# FPGA1.net
KiCad netlist of a schematic drawn in Altium Designer
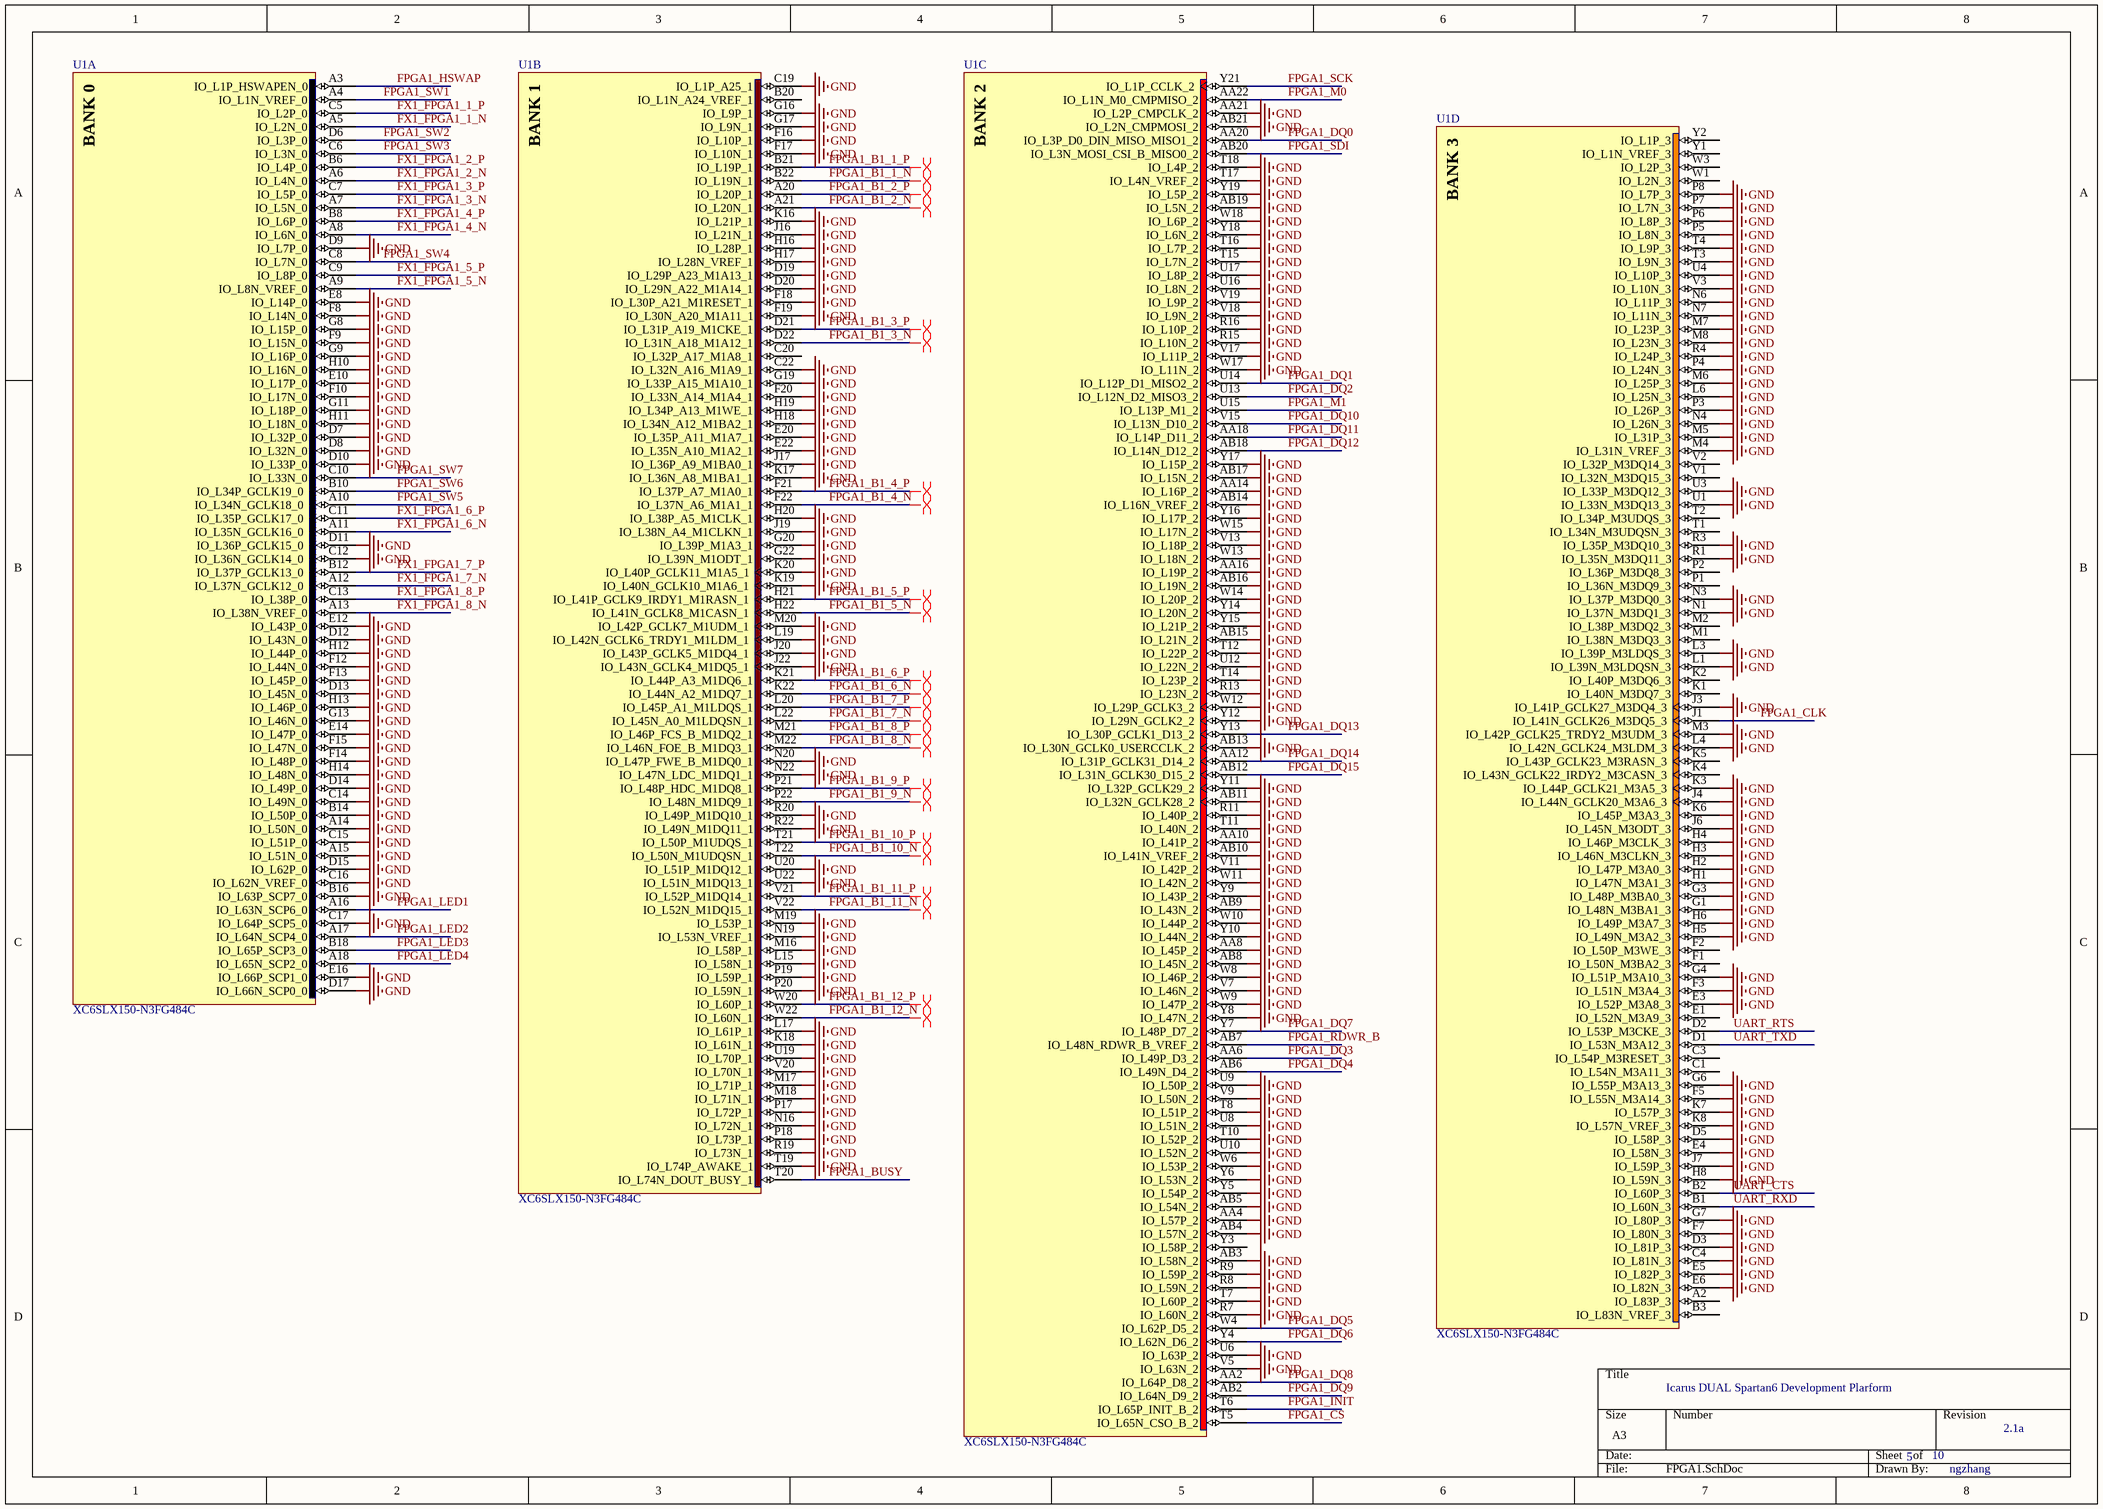
[diagram p0: FPGA1.SchDoc]

(export (version "E")
  (design (tool "Eeschema 10.0.6"))
  (components
    (comp (ref "U1")
      (value "XC6SLX150-N3FG484C")
      (footprint "FG484")
      (fields (field (name "PUBLISHER") "Altium Limited"))
      (libsource (lib "Xilinx Spartan-6") (part "XC6SLX150-N3FG484C"))
    )
  )
  (nets
    (net (code "1") (name "/FPGA1_B1_1_N") (class "Default")
      (node (ref "U1") (pin "B22") (pinfunction "IO_L19N_1_B22") (pintype "bidirectional"))
    )
    (net (code "2") (name "/FPGA1_B1_1_P") (class "Default")
      (node (ref "U1") (pin "B21") (pinfunction "IO_L19P_1_B21") (pintype "bidirectional"))
    )
    (net (code "3") (name "/FPGA1_B1_2_N") (class "Default")
      (node (ref "U1") (pin "A21") (pinfunction "IO_L20N_1_A21") (pintype "bidirectional"))
    )
    (net (code "4") (name "/FPGA1_B1_2_P") (class "Default")
      (node (ref "U1") (pin "A20") (pinfunction "IO_L20P_1_A20") (pintype "bidirectional"))
    )
    (net (code "5") (name "/FPGA1_B1_3_N") (class "Default")
      (node (ref "U1") (pin "D22") (pinfunction "IO_L31N_A18_M1A12_1_D22") (pintype "bidirectional"))
    )
    (net (code "6") (name "/FPGA1_B1_3_P") (class "Default")
      (node (ref "U1") (pin "D21") (pinfunction "IO_L31P_A19_M1CKE_1_D21") (pintype "bidirectional"))
    )
    (net (code "7") (name "/FPGA1_B1_4_N") (class "Default")
      (node (ref "U1") (pin "F22") (pinfunction "IO_L37N_A6_M1A1_1_F22") (pintype "bidirectional"))
    )
    (net (code "8") (name "/FPGA1_B1_4_P") (class "Default")
      (node (ref "U1") (pin "F21") (pinfunction "IO_L37P_A7_M1A0_1_F21") (pintype "bidirectional"))
    )
    (net (code "9") (name "/FPGA1_B1_5_N") (class "Default")
      (node (ref "U1") (pin "H22") (pinfunction "IO_L41N_GCLK8_M1CASN_1_H22") (pintype "bidirectional"))
    )
    (net (code "10") (name "/FPGA1_B1_5_P") (class "Default")
      (node (ref "U1") (pin "H21") (pinfunction "IO_L41P_GCLK9_IRDY1_M1RASN_1_H21") (pintype "bidirectional"))
    )
    (net (code "11") (name "/FPGA1_B1_6_N") (class "Default")
      (node (ref "U1") (pin "K22") (pinfunction "IO_L44N_A2_M1DQ7_1_K22") (pintype "bidirectional"))
    )
    (net (code "12") (name "/FPGA1_B1_6_P") (class "Default")
      (node (ref "U1") (pin "K21") (pinfunction "IO_L44P_A3_M1DQ6_1_K21") (pintype "bidirectional"))
    )
    (net (code "13") (name "/FPGA1_B1_7_N") (class "Default")
      (node (ref "U1") (pin "L22") (pinfunction "IO_L45N_A0_M1LDQSN_1_L22") (pintype "bidirectional"))
    )
    (net (code "14") (name "/FPGA1_B1_7_P") (class "Default")
      (node (ref "U1") (pin "L20") (pinfunction "IO_L45P_A1_M1LDQS_1_L20") (pintype "bidirectional"))
    )
    (net (code "15") (name "/FPGA1_B1_8_N") (class "Default")
      (node (ref "U1") (pin "M22") (pinfunction "IO_L46N_FOE_B_M1DQ3_1_M22") (pintype "bidirectional"))
    )
    (net (code "16") (name "/FPGA1_B1_8_P") (class "Default")
      (node (ref "U1") (pin "M21") (pinfunction "IO_L46P_FCS_B_M1DQ2_1_M21") (pintype "bidirectional"))
    )
    (net (code "17") (name "/FPGA1_B1_9_N") (class "Default")
      (node (ref "U1") (pin "P22") (pinfunction "IO_L48N_M1DQ9_1_P22") (pintype "bidirectional"))
    )
    (net (code "18") (name "/FPGA1_B1_9_P") (class "Default")
      (node (ref "U1") (pin "P21") (pinfunction "IO_L48P_HDC_M1DQ8_1_P21") (pintype "bidirectional"))
    )
    (net (code "19") (name "/FPGA1_B1_10_N") (class "Default")
      (node (ref "U1") (pin "T22") (pinfunction "IO_L50N_M1UDQSN_1_T22") (pintype "bidirectional"))
    )
    (net (code "20") (name "/FPGA1_B1_10_P") (class "Default")
      (node (ref "U1") (pin "T21") (pinfunction "IO_L50P_M1UDQS_1_T21") (pintype "bidirectional"))
    )
    (net (code "21") (name "/FPGA1_B1_11_N") (class "Default")
      (node (ref "U1") (pin "V22") (pinfunction "IO_L52N_M1DQ15_1_V22") (pintype "bidirectional"))
    )
    (net (code "22") (name "/FPGA1_B1_11_P") (class "Default")
      (node (ref "U1") (pin "V21") (pinfunction "IO_L52P_M1DQ14_1_V21") (pintype "bidirectional"))
    )
    (net (code "23") (name "/FPGA1_B1_12_N") (class "Default")
      (node (ref "U1") (pin "W22") (pinfunction "IO_L60N_1_W22") (pintype "bidirectional"))
    )
    (net (code "24") (name "/FPGA1_B1_12_P") (class "Default")
      (node (ref "U1") (pin "W20") (pinfunction "IO_L60P_1_W20") (pintype "bidirectional"))
    )
    (net (code "25") (name "/FPGA1_BUSY") (class "Default")
      (node (ref "U1") (pin "T20") (pinfunction "IO_L74N_DOUT_BUSY_1_T20") (pintype "bidirectional"))
    )
    (net (code "26") (name "/FPGA1_CLK") (class "Default")
      (node (ref "U1") (pin "J1") (pinfunction "IO_L41N_GCLK26_M3DQ5_3_J1") (pintype "bidirectional"))
    )
    (net (code "27") (name "/FPGA1_CS") (class "Default")
      (node (ref "U1") (pin "T5") (pinfunction "IO_L65N_CSO_B_2_T5") (pintype "bidirectional"))
    )
    (net (code "28") (name "/FPGA1_DQ0") (class "Default")
      (node (ref "U1") (pin "AA20") (pinfunction "IO_L3P_D0_DIN_MISO_MISO1_2_AA20") (pintype "bidirectional"))
    )
    (net (code "29") (name "/FPGA1_DQ1") (class "Default")
      (node (ref "U1") (pin "U14") (pinfunction "IO_L12P_D1_MISO2_2_U14") (pintype "bidirectional"))
    )
    (net (code "30") (name "/FPGA1_DQ2") (class "Default")
      (node (ref "U1") (pin "U13") (pinfunction "IO_L12N_D2_MISO3_2_U13") (pintype "bidirectional"))
    )
    (net (code "31") (name "/FPGA1_DQ3") (class "Default")
      (node (ref "U1") (pin "AA6") (pinfunction "IO_L49P_D3_2_AA6") (pintype "bidirectional"))
    )
    (net (code "32") (name "/FPGA1_DQ4") (class "Default")
      (node (ref "U1") (pin "AB6") (pinfunction "IO_L49N_D4_2_AB6") (pintype "bidirectional"))
    )
    (net (code "33") (name "/FPGA1_DQ5") (class "Default")
      (node (ref "U1") (pin "W4") (pinfunction "IO_L62P_D5_2_W4") (pintype "bidirectional"))
    )
    (net (code "34") (name "/FPGA1_DQ6") (class "Default")
      (node (ref "U1") (pin "Y4") (pinfunction "IO_L62N_D6_2_Y4") (pintype "bidirectional"))
    )
    (net (code "35") (name "/FPGA1_DQ7") (class "Default")
      (node (ref "U1") (pin "Y7") (pinfunction "IO_L48P_D7_2_Y7") (pintype "bidirectional"))
    )
    (net (code "36") (name "/FPGA1_DQ8") (class "Default")
      (node (ref "U1") (pin "AA2") (pinfunction "IO_L64P_D8_2_AA2") (pintype "bidirectional"))
    )
    (net (code "37") (name "/FPGA1_DQ9") (class "Default")
      (node (ref "U1") (pin "AB2") (pinfunction "IO_L64N_D9_2_AB2") (pintype "bidirectional"))
    )
    (net (code "38") (name "/FPGA1_DQ10") (class "Default")
      (node (ref "U1") (pin "V15") (pinfunction "IO_L13N_D10_2_V15") (pintype "bidirectional"))
    )
    (net (code "39") (name "/FPGA1_DQ11") (class "Default")
      (node (ref "U1") (pin "AA18") (pinfunction "IO_L14P_D11_2_AA18") (pintype "bidirectional"))
    )
    (net (code "40") (name "/FPGA1_DQ12") (class "Default")
      (node (ref "U1") (pin "AB18") (pinfunction "IO_L14N_D12_2_AB18") (pintype "bidirectional"))
    )
    (net (code "41") (name "/FPGA1_DQ13") (class "Default")
      (node (ref "U1") (pin "Y13") (pinfunction "IO_L30P_GCLK1_D13_2_Y13") (pintype "bidirectional"))
    )
    (net (code "42") (name "/FPGA1_DQ14") (class "Default")
      (node (ref "U1") (pin "AA12") (pinfunction "IO_L31P_GCLK31_D14_2_AA12") (pintype "bidirectional"))
    )
    (net (code "43") (name "/FPGA1_DQ15") (class "Default")
      (node (ref "U1") (pin "AB12") (pinfunction "IO_L31N_GCLK30_D15_2_AB12") (pintype "bidirectional"))
    )
    (net (code "44") (name "/FPGA1_HSWAP") (class "Default")
      (node (ref "U1") (pin "A3") (pinfunction "IO_L1P_HSWAPEN_0_A3") (pintype "bidirectional"))
    )
    (net (code "45") (name "/FPGA1_INIT") (class "Default")
      (node (ref "U1") (pin "T6") (pinfunction "IO_L65P_INIT_B_2_T6") (pintype "bidirectional"))
    )
    (net (code "46") (name "/FPGA1_LED1") (class "Default")
      (node (ref "U1") (pin "A16") (pinfunction "IO_L63N_SCP6_0_A16") (pintype "bidirectional"))
    )
    (net (code "47") (name "/FPGA1_LED2") (class "Default")
      (node (ref "U1") (pin "A17") (pinfunction "IO_L64N_SCP4_0_A17") (pintype "bidirectional"))
    )
    (net (code "48") (name "/FPGA1_LED3") (class "Default")
      (node (ref "U1") (pin "B18") (pinfunction "IO_L65P_SCP3_0_B18") (pintype "bidirectional"))
    )
    (net (code "49") (name "/FPGA1_LED4") (class "Default")
      (node (ref "U1") (pin "A18") (pinfunction "IO_L65N_SCP2_0_A18") (pintype "bidirectional"))
    )
    (net (code "50") (name "/FPGA1_M0") (class "Default")
      (node (ref "U1") (pin "AA22") (pinfunction "IO_L1N_M0_CMPMISO_2_AA22") (pintype "bidirectional"))
    )
    (net (code "51") (name "/FPGA1_M1") (class "Default")
      (node (ref "U1") (pin "U15") (pinfunction "IO_L13P_M1_2_U15") (pintype "bidirectional"))
    )
    (net (code "52") (name "/FPGA1_RDWR_B") (class "Default")
      (node (ref "U1") (pin "AB7") (pinfunction "IO_L48N_RDWR_B_VREF_2_AB7") (pintype "bidirectional"))
    )
    (net (code "53") (name "/FPGA1_SCK") (class "Default")
      (node (ref "U1") (pin "Y21") (pinfunction "IO_L1P_CCLK_2_Y21") (pintype "bidirectional"))
    )
    (net (code "54") (name "/FPGA1_SDI") (class "Default")
      (node (ref "U1") (pin "AB20") (pinfunction "IO_L3N_MOSI_CSI_B_MISO0_2_AB20") (pintype "bidirectional"))
    )
    (net (code "55") (name "/FPGA1_SW1") (class "Default")
      (node (ref "U1") (pin "A4") (pinfunction "IO_L1N_VREF_0_A4") (pintype "bidirectional"))
    )
    (net (code "56") (name "/FPGA1_SW2") (class "Default")
      (node (ref "U1") (pin "D6") (pinfunction "IO_L3P_0_D6") (pintype "bidirectional"))
    )
    (net (code "57") (name "/FPGA1_SW3") (class "Default")
      (node (ref "U1") (pin "C6") (pinfunction "IO_L3N_0_C6") (pintype "bidirectional"))
    )
    (net (code "58") (name "/FPGA1_SW4") (class "Default")
      (node (ref "U1") (pin "C8") (pinfunction "IO_L7N_0_C8") (pintype "bidirectional"))
    )
    (net (code "59") (name "/FPGA1_SW5") (class "Default")
      (node (ref "U1") (pin "A10") (pinfunction "IO_L34N_GCLK18_0_A10") (pintype "bidirectional"))
    )
    (net (code "60") (name "/FPGA1_SW6") (class "Default")
      (node (ref "U1") (pin "B10") (pinfunction "IO_L34P_GCLK19_0_B10") (pintype "bidirectional"))
    )
    (net (code "61") (name "/FPGA1_SW7") (class "Default")
      (node (ref "U1") (pin "C10") (pinfunction "IO_L33N_0_C10") (pintype "bidirectional"))
    )
    (net (code "62") (name "/FX1_FPGA1_1_N") (class "Default")
      (node (ref "U1") (pin "A5") (pinfunction "IO_L2N_0_A5") (pintype "bidirectional"))
    )
    (net (code "63") (name "/FX1_FPGA1_1_P") (class "Default")
      (node (ref "U1") (pin "C5") (pinfunction "IO_L2P_0_C5") (pintype "bidirectional"))
    )
    (net (code "64") (name "/FX1_FPGA1_2_N") (class "Default")
      (node (ref "U1") (pin "A6") (pinfunction "IO_L4N_0_A6") (pintype "bidirectional"))
    )
    (net (code "65") (name "/FX1_FPGA1_2_P") (class "Default")
      (node (ref "U1") (pin "B6") (pinfunction "IO_L4P_0_B6") (pintype "bidirectional"))
    )
    (net (code "66") (name "/FX1_FPGA1_3_N") (class "Default")
      (node (ref "U1") (pin "A7") (pinfunction "IO_L5N_0_A7") (pintype "bidirectional"))
    )
    (net (code "67") (name "/FX1_FPGA1_3_P") (class "Default")
      (node (ref "U1") (pin "C7") (pinfunction "IO_L5P_0_C7") (pintype "bidirectional"))
    )
    (net (code "68") (name "/FX1_FPGA1_4_N") (class "Default")
      (node (ref "U1") (pin "A8") (pinfunction "IO_L6N_0_A8") (pintype "bidirectional"))
    )
    (net (code "69") (name "/FX1_FPGA1_4_P") (class "Default")
      (node (ref "U1") (pin "B8") (pinfunction "IO_L6P_0_B8") (pintype "bidirectional"))
    )
    (net (code "70") (name "/FX1_FPGA1_5_N") (class "Default")
      (node (ref "U1") (pin "A9") (pinfunction "IO_L8N_VREF_0_A9") (pintype "bidirectional"))
    )
    (net (code "71") (name "/FX1_FPGA1_5_P") (class "Default")
      (node (ref "U1") (pin "C9") (pinfunction "IO_L8P_0_C9") (pintype "bidirectional"))
    )
    (net (code "72") (name "/FX1_FPGA1_6_N") (class "Default")
      (node (ref "U1") (pin "A11") (pinfunction "IO_L35N_GCLK16_0_A11") (pintype "bidirectional"))
    )
    (net (code "73") (name "/FX1_FPGA1_6_P") (class "Default")
      (node (ref "U1") (pin "C11") (pinfunction "IO_L35P_GCLK17_0_C11") (pintype "bidirectional"))
    )
    (net (code "74") (name "/FX1_FPGA1_7_N") (class "Default")
      (node (ref "U1") (pin "A12") (pinfunction "IO_L37N_GCLK12_0_A12") (pintype "bidirectional"))
    )
    (net (code "75") (name "/FX1_FPGA1_7_P") (class "Default")
      (node (ref "U1") (pin "B12") (pinfunction "IO_L37P_GCLK13_0_B12") (pintype "bidirectional"))
    )
    (net (code "76") (name "/FX1_FPGA1_8_N") (class "Default")
      (node (ref "U1") (pin "A13") (pinfunction "IO_L38N_VREF_0_A13") (pintype "bidirectional"))
    )
    (net (code "77") (name "/FX1_FPGA1_8_P") (class "Default")
      (node (ref "U1") (pin "C13") (pinfunction "IO_L38P_0_C13") (pintype "bidirectional"))
    )
    (net (code "78") (name "/UART_CTS") (class "Default")
      (node (ref "U1") (pin "B2") (pinfunction "IO_L60P_3_B2") (pintype "bidirectional"))
    )
    (net (code "79") (name "/UART_RTS") (class "Default")
      (node (ref "U1") (pin "D2") (pinfunction "IO_L53P_M3CKE_3_D2") (pintype "bidirectional"))
    )
    (net (code "80") (name "/UART_RXD") (class "Default")
      (node (ref "U1") (pin "B1") (pinfunction "IO_L60N_3_B1") (pintype "bidirectional"))
    )
    (net (code "81") (name "/UART_TXD") (class "Default")
      (node (ref "U1") (pin "D1") (pinfunction "IO_L53N_M3A12_3_D1") (pintype "bidirectional"))
    )
    (net (code "82") (name "GND") (class "Default")
      (node (ref "U1") (pin "A14") (pinfunction "IO_L50N_0_A14") (pintype "bidirectional"))
      (node (ref "U1") (pin "A15") (pinfunction "IO_L51N_0_A15") (pintype "bidirectional"))
      (node (ref "U1") (pin "AA10") (pinfunction "IO_L41P_2_AA10") (pintype "bidirectional"))
      (node (ref "U1") (pin "AA14") (pinfunction "IO_L16P_2_AA14") (pintype "bidirectional"))
      (node (ref "U1") (pin "AA16") (pinfunction "IO_L19P_2_AA16") (pintype "bidirectional"))
      (node (ref "U1") (pin "AA21") (pinfunction "IO_L2P_CMPCLK_2_AA21") (pintype "bidirectional"))
      (node (ref "U1") (pin "AA4") (pinfunction "IO_L57P_2_AA4") (pintype "bidirectional"))
      (node (ref "U1") (pin "AA8") (pinfunction "IO_L45P_2_AA8") (pintype "bidirectional"))
      (node (ref "U1") (pin "AB10") (pinfunction "IO_L41N_VREF_2_AB10") (pintype "bidirectional"))
      (node (ref "U1") (pin "AB11") (pinfunction "IO_L32N_GCLK28_2_AB11") (pintype "bidirectional"))
      (node (ref "U1") (pin "AB13") (pinfunction "IO_L30N_GCLK0_USERCCLK_2_AB13") (pintype "bidirectional"))
      (node (ref "U1") (pin "AB14") (pinfunction "IO_L16N_VREF_2_AB14") (pintype "bidirectional"))
      (node (ref "U1") (pin "AB15") (pinfunction "IO_L21N_2_AB15") (pintype "bidirectional"))
      (node (ref "U1") (pin "AB16") (pinfunction "IO_L19N_2_AB16") (pintype "bidirectional"))
      (node (ref "U1") (pin "AB17") (pinfunction "IO_L15N_2_AB17") (pintype "bidirectional"))
      (node (ref "U1") (pin "AB19") (pinfunction "IO_L5N_2_AB19") (pintype "bidirectional"))
      (node (ref "U1") (pin "AB21") (pinfunction "IO_L2N_CMPMOSI_2_AB21") (pintype "bidirectional"))
      (node (ref "U1") (pin "AB3") (pinfunction "IO_L58N_2_AB3") (pintype "bidirectional"))
      (node (ref "U1") (pin "AB4") (pinfunction "IO_L57N_2_AB4") (pintype "bidirectional"))
      (node (ref "U1") (pin "AB5") (pinfunction "IO_L54N_2_AB5") (pintype "bidirectional"))
      (node (ref "U1") (pin "AB8") (pinfunction "IO_L45N_2_AB8") (pintype "bidirectional"))
      (node (ref "U1") (pin "AB9") (pinfunction "IO_L43N_2_AB9") (pintype "bidirectional"))
      (node (ref "U1") (pin "B14") (pinfunction "IO_L50P_0_B14") (pintype "bidirectional"))
      (node (ref "U1") (pin "B16") (pinfunction "IO_L63P_SCP7_0_B16") (pintype "bidirectional"))
      (node (ref "U1") (pin "C12") (pinfunction "IO_L36N_GCLK14_0_C12") (pintype "bidirectional"))
      (node (ref "U1") (pin "C14") (pinfunction "IO_L49N_0_C14") (pintype "bidirectional"))
      (node (ref "U1") (pin "C15") (pinfunction "IO_L51P_0_C15") (pintype "bidirectional"))
      (node (ref "U1") (pin "C16") (pinfunction "IO_L62N_VREF_0_C16") (pintype "bidirectional"))
      (node (ref "U1") (pin "C17") (pinfunction "IO_L64P_SCP5_0_C17") (pintype "bidirectional"))
      (node (ref "U1") (pin "C19") (pinfunction "IO_L1P_A25_1_C19") (pintype "bidirectional"))
      (node (ref "U1") (pin "C22") (pinfunction "IO_L32N_A16_M1A9_1_C22") (pintype "bidirectional"))
      (node (ref "U1") (pin "C4") (pinfunction "IO_L81N_3_C4") (pintype "bidirectional"))
      (node (ref "U1") (pin "D10") (pinfunction "IO_L33P_0_D10") (pintype "bidirectional"))
      (node (ref "U1") (pin "D11") (pinfunction "IO_L36P_GCLK15_0_D11") (pintype "bidirectional"))
      (node (ref "U1") (pin "D12") (pinfunction "IO_L43N_0_D12") (pintype "bidirectional"))
      (node (ref "U1") (pin "D13") (pinfunction "IO_L45N_0_D13") (pintype "bidirectional"))
      (node (ref "U1") (pin "D14") (pinfunction "IO_L49P_0_D14") (pintype "bidirectional"))
      (node (ref "U1") (pin "D15") (pinfunction "IO_L62P_0_D15") (pintype "bidirectional"))
      (node (ref "U1") (pin "D17") (pinfunction "IO_L66N_SCP0_0_D17") (pintype "bidirectional"))
      (node (ref "U1") (pin "D19") (pinfunction "IO_L29P_A23_M1A13_1_D19") (pintype "bidirectional"))
      (node (ref "U1") (pin "D20") (pinfunction "IO_L29N_A22_M1A14_1_D20") (pintype "bidirectional"))
      (node (ref "U1") (pin "D3") (pinfunction "IO_L81P_3_D3") (pintype "bidirectional"))
      (node (ref "U1") (pin "D5") (pinfunction "IO_L58P_3_D5") (pintype "bidirectional"))
      (node (ref "U1") (pin "D7") (pinfunction "IO_L32P_0_D7") (pintype "bidirectional"))
      (node (ref "U1") (pin "D8") (pinfunction "IO_L32N_0_D8") (pintype "bidirectional"))
      (node (ref "U1") (pin "D9") (pinfunction "IO_L7P_0_D9") (pintype "bidirectional"))
      (node (ref "U1") (pin "E10") (pinfunction "IO_L17P_0_E10") (pintype "bidirectional"))
      (node (ref "U1") (pin "E12") (pinfunction "IO_L43P_0_E12") (pintype "bidirectional"))
      (node (ref "U1") (pin "E14") (pinfunction "IO_L47P_0_E14") (pintype "bidirectional"))
      (node (ref "U1") (pin "E16") (pinfunction "IO_L66P_SCP1_0_E16") (pintype "bidirectional"))
      (node (ref "U1") (pin "E20") (pinfunction "IO_L35P_A11_M1A7_1_E20") (pintype "bidirectional"))
      (node (ref "U1") (pin "E22") (pinfunction "IO_L35N_A10_M1A2_1_E22") (pintype "bidirectional"))
      (node (ref "U1") (pin "E3") (pinfunction "IO_L52P_M3A8_3_E3") (pintype "bidirectional"))
      (node (ref "U1") (pin "E4") (pinfunction "IO_L58N_3_E4") (pintype "bidirectional"))
      (node (ref "U1") (pin "E5") (pinfunction "IO_L82P_3_E5") (pintype "bidirectional"))
      (node (ref "U1") (pin "E6") (pinfunction "IO_L82N_3_E6") (pintype "bidirectional"))
      (node (ref "U1") (pin "E8") (pinfunction "IO_L14P_0_E8") (pintype "bidirectional"))
      (node (ref "U1") (pin "F10") (pinfunction "IO_L17N_0_F10") (pintype "bidirectional"))
      (node (ref "U1") (pin "F12") (pinfunction "IO_L44N_0_F12") (pintype "bidirectional"))
      (node (ref "U1") (pin "F13") (pinfunction "IO_L45P_0_F13") (pintype "bidirectional"))
      (node (ref "U1") (pin "F14") (pinfunction "IO_L48P_0_F14") (pintype "bidirectional"))
      (node (ref "U1") (pin "F15") (pinfunction "IO_L47N_0_F15") (pintype "bidirectional"))
      (node (ref "U1") (pin "F16") (pinfunction "IO_L10P_1_F16") (pintype "bidirectional"))
      (node (ref "U1") (pin "F17") (pinfunction "IO_L10N_1_F17") (pintype "bidirectional"))
      (node (ref "U1") (pin "F18") (pinfunction "IO_L30P_A21_M1RESET_1_F18") (pintype "bidirectional"))
      (node (ref "U1") (pin "F19") (pinfunction "IO_L30N_A20_M1A11_1_F19") (pintype "bidirectional"))
      (node (ref "U1") (pin "F20") (pinfunction "IO_L33N_A14_M1A4_1_F20") (pintype "bidirectional"))
      (node (ref "U1") (pin "F3") (pinfunction "IO_L51N_M3A4_3_F3") (pintype "bidirectional"))
      (node (ref "U1") (pin "F5") (pinfunction "IO_L55N_M3A14_3_F5") (pintype "bidirectional"))
      (node (ref "U1") (pin "F7") (pinfunction "IO_L80N_3_F7") (pintype "bidirectional"))
      (node (ref "U1") (pin "F8") (pinfunction "IO_L14N_0_F8") (pintype "bidirectional"))
      (node (ref "U1") (pin "F9") (pinfunction "IO_L15N_0_F9") (pintype "bidirectional"))
      (node (ref "U1") (pin "G1") (pinfunction "IO_L48N_M3BA1_3_G1") (pintype "bidirectional"))
      (node (ref "U1") (pin "G11") (pinfunction "IO_L18P_0_G11") (pintype "bidirectional"))
      (node (ref "U1") (pin "G13") (pinfunction "IO_L46N_0_G13") (pintype "bidirectional"))
      (node (ref "U1") (pin "G16") (pinfunction "IO_L9P_1_G16") (pintype "bidirectional"))
      (node (ref "U1") (pin "G17") (pinfunction "IO_L9N_1_G17") (pintype "bidirectional"))
      (node (ref "U1") (pin "G19") (pinfunction "IO_L33P_A15_M1A10_1_G19") (pintype "bidirectional"))
      (node (ref "U1") (pin "G20") (pinfunction "IO_L39P_M1A3_1_G20") (pintype "bidirectional"))
      (node (ref "U1") (pin "G22") (pinfunction "IO_L39N_M1ODT_1_G22") (pintype "bidirectional"))
      (node (ref "U1") (pin "G3") (pinfunction "IO_L48P_M3BA0_3_G3") (pintype "bidirectional"))
      (node (ref "U1") (pin "G4") (pinfunction "IO_L51P_M3A10_3_G4") (pintype "bidirectional"))
      (node (ref "U1") (pin "G6") (pinfunction "IO_L55P_M3A13_3_G6") (pintype "bidirectional"))
      (node (ref "U1") (pin "G7") (pinfunction "IO_L80P_3_G7") (pintype "bidirectional"))
      (node (ref "U1") (pin "G8") (pinfunction "IO_L15P_0_G8") (pintype "bidirectional"))
      (node (ref "U1") (pin "G9") (pinfunction "IO_L16P_0_G9") (pintype "bidirectional"))
      (node (ref "U1") (pin "H1") (pinfunction "IO_L47N_M3A1_3_H1") (pintype "bidirectional"))
      (node (ref "U1") (pin "H10") (pinfunction "IO_L16N_0_H10") (pintype "bidirectional"))
      (node (ref "U1") (pin "H11") (pinfunction "IO_L18N_0_H11") (pintype "bidirectional"))
      (node (ref "U1") (pin "H12") (pinfunction "IO_L44P_0_H12") (pintype "bidirectional"))
      (node (ref "U1") (pin "H13") (pinfunction "IO_L46P_0_H13") (pintype "bidirectional"))
      (node (ref "U1") (pin "H14") (pinfunction "IO_L48N_0_H14") (pintype "bidirectional"))
      (node (ref "U1") (pin "H16") (pinfunction "IO_L28P_1_H16") (pintype "bidirectional"))
      (node (ref "U1") (pin "H17") (pinfunction "IO_L28N_VREF_1_H17") (pintype "bidirectional"))
      (node (ref "U1") (pin "H18") (pinfunction "IO_L34N_A12_M1BA2_1_H18") (pintype "bidirectional"))
      (node (ref "U1") (pin "H19") (pinfunction "IO_L34P_A13_M1WE_1_H19") (pintype "bidirectional"))
      (node (ref "U1") (pin "H2") (pinfunction "IO_L47P_M3A0_3_H2") (pintype "bidirectional"))
      (node (ref "U1") (pin "H20") (pinfunction "IO_L38P_A5_M1CLK_1_H20") (pintype "bidirectional"))
      (node (ref "U1") (pin "H3") (pinfunction "IO_L46N_M3CLKN_3_H3") (pintype "bidirectional"))
      (node (ref "U1") (pin "H4") (pinfunction "IO_L46P_M3CLK_3_H4") (pintype "bidirectional"))
      (node (ref "U1") (pin "H5") (pinfunction "IO_L49N_M3A2_3_H5") (pintype "bidirectional"))
      (node (ref "U1") (pin "H6") (pinfunction "IO_L49P_M3A7_3_H6") (pintype "bidirectional"))
      (node (ref "U1") (pin "H8") (pinfunction "IO_L59N_3_H8") (pintype "bidirectional"))
      (node (ref "U1") (pin "J16") (pinfunction "IO_L21N_1_J16") (pintype "bidirectional"))
      (node (ref "U1") (pin "J17") (pinfunction "IO_L36P_A9_M1BA0_1_J17") (pintype "bidirectional"))
      (node (ref "U1") (pin "J19") (pinfunction "IO_L38N_A4_M1CLKN_1_J19") (pintype "bidirectional"))
      (node (ref "U1") (pin "J20") (pinfunction "IO_L43P_GCLK5_M1DQ4_1_J20") (pintype "bidirectional"))
      (node (ref "U1") (pin "J22") (pinfunction "IO_L43N_GCLK4_M1DQ5_1_J22") (pintype "bidirectional"))
      (node (ref "U1") (pin "J3") (pinfunction "IO_L41P_GCLK27_M3DQ4_3_J3") (pintype "bidirectional"))
      (node (ref "U1") (pin "J4") (pinfunction "IO_L44N_GCLK20_M3A6_3_J4") (pintype "bidirectional"))
      (node (ref "U1") (pin "J6") (pinfunction "IO_L45N_M3ODT_3_J6") (pintype "bidirectional"))
      (node (ref "U1") (pin "J7") (pinfunction "IO_L59P_3_J7") (pintype "bidirectional"))
      (node (ref "U1") (pin "K16") (pinfunction "IO_L21P_1_K16") (pintype "bidirectional"))
      (node (ref "U1") (pin "K17") (pinfunction "IO_L36N_A8_M1BA1_1_K17") (pintype "bidirectional"))
      (node (ref "U1") (pin "K18") (pinfunction "IO_L61N_1_K18") (pintype "bidirectional"))
      (node (ref "U1") (pin "K19") (pinfunction "IO_L40N_GCLK10_M1A6_1_K19") (pintype "bidirectional"))
      (node (ref "U1") (pin "K20") (pinfunction "IO_L40P_GCLK11_M1A5_1_K20") (pintype "bidirectional"))
      (node (ref "U1") (pin "K3") (pinfunction "IO_L44P_GCLK21_M3A5_3_K3") (pintype "bidirectional"))
      (node (ref "U1") (pin "K6") (pinfunction "IO_L45P_M3A3_3_K6") (pintype "bidirectional"))
      (node (ref "U1") (pin "K7") (pinfunction "IO_L57P_3_K7") (pintype "bidirectional"))
      (node (ref "U1") (pin "K8") (pinfunction "IO_L57N_VREF_3_K8") (pintype "bidirectional"))
      (node (ref "U1") (pin "L1") (pinfunction "IO_L39N_M3LDQSN_3_L1") (pintype "bidirectional"))
      (node (ref "U1") (pin "L15") (pinfunction "IO_L58N_1_L15") (pintype "bidirectional"))
      (node (ref "U1") (pin "L17") (pinfunction "IO_L61P_1_L17") (pintype "bidirectional"))
      (node (ref "U1") (pin "L19") (pinfunction "IO_L42N_GCLK6_TRDY1_M1LDM_1_L19") (pintype "bidirectional"))
      (node (ref "U1") (pin "L3") (pinfunction "IO_L39P_M3LDQS_3_L3") (pintype "bidirectional"))
      (node (ref "U1") (pin "L4") (pinfunction "IO_L42N_GCLK24_M3LDM_3_L4") (pintype "bidirectional"))
      (node (ref "U1") (pin "L6") (pinfunction "IO_L25N_3_L6") (pintype "bidirectional"))
      (node (ref "U1") (pin "M16") (pinfunction "IO_L58P_1_M16") (pintype "bidirectional"))
      (node (ref "U1") (pin "M17") (pinfunction "IO_L71P_1_M17") (pintype "bidirectional"))
      (node (ref "U1") (pin "M18") (pinfunction "IO_L71N_1_M18") (pintype "bidirectional"))
      (node (ref "U1") (pin "M19") (pinfunction "IO_L53P_1_M19") (pintype "bidirectional"))
      (node (ref "U1") (pin "M20") (pinfunction "IO_L42P_GCLK7_M1UDM_1_M20") (pintype "bidirectional"))
      (node (ref "U1") (pin "M3") (pinfunction "IO_L42P_GCLK25_TRDY2_M3UDM_3_M3") (pintype "bidirectional"))
      (node (ref "U1") (pin "M4") (pinfunction "IO_L31N_VREF_3_M4") (pintype "bidirectional"))
      (node (ref "U1") (pin "M5") (pinfunction "IO_L31P_3_M5") (pintype "bidirectional"))
      (node (ref "U1") (pin "M6") (pinfunction "IO_L25P_3_M6") (pintype "bidirectional"))
      (node (ref "U1") (pin "M7") (pinfunction "IO_L23P_3_M7") (pintype "bidirectional"))
      (node (ref "U1") (pin "M8") (pinfunction "IO_L23N_3_M8") (pintype "bidirectional"))
      (node (ref "U1") (pin "N1") (pinfunction "IO_L37N_M3DQ1_3_N1") (pintype "bidirectional"))
      (node (ref "U1") (pin "N16") (pinfunction "IO_L72N_1_N16") (pintype "bidirectional"))
      (node (ref "U1") (pin "N19") (pinfunction "IO_L53N_VREF_1_N19") (pintype "bidirectional"))
      (node (ref "U1") (pin "N20") (pinfunction "IO_L47P_FWE_B_M1DQ0_1_N20") (pintype "bidirectional"))
      (node (ref "U1") (pin "N22") (pinfunction "IO_L47N_LDC_M1DQ1_1_N22") (pintype "bidirectional"))
      (node (ref "U1") (pin "N3") (pinfunction "IO_L37P_M3DQ0_3_N3") (pintype "bidirectional"))
      (node (ref "U1") (pin "N4") (pinfunction "IO_L26N_3_N4") (pintype "bidirectional"))
      (node (ref "U1") (pin "N6") (pinfunction "IO_L11P_3_N6") (pintype "bidirectional"))
      (node (ref "U1") (pin "N7") (pinfunction "IO_L11N_3_N7") (pintype "bidirectional"))
      (node (ref "U1") (pin "P17") (pinfunction "IO_L72P_1_P17") (pintype "bidirectional"))
      (node (ref "U1") (pin "P18") (pinfunction "IO_L73P_1_P18") (pintype "bidirectional"))
      (node (ref "U1") (pin "P19") (pinfunction "IO_L59P_1_P19") (pintype "bidirectional"))
      (node (ref "U1") (pin "P20") (pinfunction "IO_L59N_1_P20") (pintype "bidirectional"))
      (node (ref "U1") (pin "P3") (pinfunction "IO_L26P_3_P3") (pintype "bidirectional"))
      (node (ref "U1") (pin "P4") (pinfunction "IO_L24N_3_P4") (pintype "bidirectional"))
      (node (ref "U1") (pin "P5") (pinfunction "IO_L8N_3_P5") (pintype "bidirectional"))
      (node (ref "U1") (pin "P6") (pinfunction "IO_L8P_3_P6") (pintype "bidirectional"))
      (node (ref "U1") (pin "P7") (pinfunction "IO_L7N_3_P7") (pintype "bidirectional"))
      (node (ref "U1") (pin "P8") (pinfunction "IO_L7P_3_P8") (pintype "bidirectional"))
      (node (ref "U1") (pin "R1") (pinfunction "IO_L35N_M3DQ11_3_R1") (pintype "bidirectional"))
      (node (ref "U1") (pin "R11") (pinfunction "IO_L40P_2_R11") (pintype "bidirectional"))
      (node (ref "U1") (pin "R13") (pinfunction "IO_L23N_2_R13") (pintype "bidirectional"))
      (node (ref "U1") (pin "R15") (pinfunction "IO_L10N_2_R15") (pintype "bidirectional"))
      (node (ref "U1") (pin "R16") (pinfunction "IO_L10P_2_R16") (pintype "bidirectional"))
      (node (ref "U1") (pin "R19") (pinfunction "IO_L73N_1_R19") (pintype "bidirectional"))
      (node (ref "U1") (pin "R20") (pinfunction "IO_L49P_M1DQ10_1_R20") (pintype "bidirectional"))
      (node (ref "U1") (pin "R22") (pinfunction "IO_L49N_M1DQ11_1_R22") (pintype "bidirectional"))
      (node (ref "U1") (pin "R3") (pinfunction "IO_L35P_M3DQ10_3_R3") (pintype "bidirectional"))
      (node (ref "U1") (pin "R4") (pinfunction "IO_L24P_3_R4") (pintype "bidirectional"))
      (node (ref "U1") (pin "R7") (pinfunction "IO_L60N_2_R7") (pintype "bidirectional"))
      (node (ref "U1") (pin "R8") (pinfunction "IO_L59N_2_R8") (pintype "bidirectional"))
      (node (ref "U1") (pin "R9") (pinfunction "IO_L59P_2_R9") (pintype "bidirectional"))
      (node (ref "U1") (pin "T10") (pinfunction "IO_L52P_2_T10") (pintype "bidirectional"))
      (node (ref "U1") (pin "T11") (pinfunction "IO_L40N_2_T11") (pintype "bidirectional"))
      (node (ref "U1") (pin "T12") (pinfunction "IO_L22P_2_T12") (pintype "bidirectional"))
      (node (ref "U1") (pin "T14") (pinfunction "IO_L23P_2_T14") (pintype "bidirectional"))
      (node (ref "U1") (pin "T15") (pinfunction "IO_L7N_2_T15") (pintype "bidirectional"))
      (node (ref "U1") (pin "T16") (pinfunction "IO_L7P_2_T16") (pintype "bidirectional"))
      (node (ref "U1") (pin "T17") (pinfunction "IO_L4N_VREF_2_T17") (pintype "bidirectional"))
      (node (ref "U1") (pin "T18") (pinfunction "IO_L4P_2_T18") (pintype "bidirectional"))
      (node (ref "U1") (pin "T19") (pinfunction "IO_L74P_AWAKE_1_T19") (pintype "bidirectional"))
      (node (ref "U1") (pin "T3") (pinfunction "IO_L9N_3_T3") (pintype "bidirectional"))
      (node (ref "U1") (pin "T4") (pinfunction "IO_L9P_3_T4") (pintype "bidirectional"))
      (node (ref "U1") (pin "T7") (pinfunction "IO_L60P_2_T7") (pintype "bidirectional"))
      (node (ref "U1") (pin "T8") (pinfunction "IO_L51P_2_T8") (pintype "bidirectional"))
      (node (ref "U1") (pin "U1") (pinfunction "IO_L33N_M3DQ13_3_U1") (pintype "bidirectional"))
      (node (ref "U1") (pin "U10") (pinfunction "IO_L52N_2_U10") (pintype "bidirectional"))
      (node (ref "U1") (pin "U12") (pinfunction "IO_L22N_2_U12") (pintype "bidirectional"))
      (node (ref "U1") (pin "U16") (pinfunction "IO_L8N_2_U16") (pintype "bidirectional"))
      (node (ref "U1") (pin "U17") (pinfunction "IO_L8P_2_U17") (pintype "bidirectional"))
      (node (ref "U1") (pin "U19") (pinfunction "IO_L70P_1_U19") (pintype "bidirectional"))
      (node (ref "U1") (pin "U20") (pinfunction "IO_L51P_M1DQ12_1_U20") (pintype "bidirectional"))
      (node (ref "U1") (pin "U22") (pinfunction "IO_L51N_M1DQ13_1_U22") (pintype "bidirectional"))
      (node (ref "U1") (pin "U3") (pinfunction "IO_L33P_M3DQ12_3_U3") (pintype "bidirectional"))
      (node (ref "U1") (pin "U4") (pinfunction "IO_L10P_3_U4") (pintype "bidirectional"))
      (node (ref "U1") (pin "U6") (pinfunction "IO_L63P_2_U6") (pintype "bidirectional"))
      (node (ref "U1") (pin "U8") (pinfunction "IO_L51N_2_U8") (pintype "bidirectional"))
      (node (ref "U1") (pin "U9") (pinfunction "IO_L50P_2_U9") (pintype "bidirectional"))
      (node (ref "U1") (pin "V11") (pinfunction "IO_L42P_2_V11") (pintype "bidirectional"))
      (node (ref "U1") (pin "V13") (pinfunction "IO_L18P_2_V13") (pintype "bidirectional"))
      (node (ref "U1") (pin "V17") (pinfunction "IO_L11P_2_V17") (pintype "bidirectional"))
      (node (ref "U1") (pin "V18") (pinfunction "IO_L9N_2_V18") (pintype "bidirectional"))
      (node (ref "U1") (pin "V19") (pinfunction "IO_L9P_2_V19") (pintype "bidirectional"))
      (node (ref "U1") (pin "V20") (pinfunction "IO_L70N_1_V20") (pintype "bidirectional"))
      (node (ref "U1") (pin "V3") (pinfunction "IO_L10N_3_V3") (pintype "bidirectional"))
      (node (ref "U1") (pin "V5") (pinfunction "IO_L63N_2_V5") (pintype "bidirectional"))
      (node (ref "U1") (pin "V7") (pinfunction "IO_L46N_2_V7") (pintype "bidirectional"))
      (node (ref "U1") (pin "V9") (pinfunction "IO_L50N_2_V9") (pintype "bidirectional"))
      (node (ref "U1") (pin "W10") (pinfunction "IO_L44P_2_W10") (pintype "bidirectional"))
      (node (ref "U1") (pin "W11") (pinfunction "IO_L42N_2_W11") (pintype "bidirectional"))
      (node (ref "U1") (pin "W12") (pinfunction "IO_L29P_GCLK3_2_W12") (pintype "bidirectional"))
      (node (ref "U1") (pin "W13") (pinfunction "IO_L18N_2_W13") (pintype "bidirectional"))
      (node (ref "U1") (pin "W14") (pinfunction "IO_L20P_2_W14") (pintype "bidirectional"))
      (node (ref "U1") (pin "W15") (pinfunction "IO_L17N_2_W15") (pintype "bidirectional"))
      (node (ref "U1") (pin "W17") (pinfunction "IO_L11N_2_W17") (pintype "bidirectional"))
      (node (ref "U1") (pin "W18") (pinfunction "IO_L6P_2_W18") (pintype "bidirectional"))
      (node (ref "U1") (pin "W6") (pinfunction "IO_L53P_2_W6") (pintype "bidirectional"))
      (node (ref "U1") (pin "W8") (pinfunction "IO_L46P_2_W8") (pintype "bidirectional"))
      (node (ref "U1") (pin "W9") (pinfunction "IO_L47P_2_W9") (pintype "bidirectional"))
      (node (ref "U1") (pin "Y10") (pinfunction "IO_L44N_2_Y10") (pintype "bidirectional"))
      (node (ref "U1") (pin "Y11") (pinfunction "IO_L32P_GCLK29_2_Y11") (pintype "bidirectional"))
      (node (ref "U1") (pin "Y12") (pinfunction "IO_L29N_GCLK2_2_Y12") (pintype "bidirectional"))
      (node (ref "U1") (pin "Y14") (pinfunction "IO_L20N_2_Y14") (pintype "bidirectional"))
      (node (ref "U1") (pin "Y15") (pinfunction "IO_L21P_2_Y15") (pintype "bidirectional"))
      (node (ref "U1") (pin "Y16") (pinfunction "IO_L17P_2_Y16") (pintype "bidirectional"))
      (node (ref "U1") (pin "Y17") (pinfunction "IO_L15P_2_Y17") (pintype "bidirectional"))
      (node (ref "U1") (pin "Y18") (pinfunction "IO_L6N_2_Y18") (pintype "bidirectional"))
      (node (ref "U1") (pin "Y19") (pinfunction "IO_L5P_2_Y19") (pintype "bidirectional"))
      (node (ref "U1") (pin "Y5") (pinfunction "IO_L54P_2_Y5") (pintype "bidirectional"))
      (node (ref "U1") (pin "Y6") (pinfunction "IO_L53N_2_Y6") (pintype "bidirectional"))
      (node (ref "U1") (pin "Y8") (pinfunction "IO_L47N_2_Y8") (pintype "bidirectional"))
      (node (ref "U1") (pin "Y9") (pinfunction "IO_L43P_2_Y9") (pintype "bidirectional"))
    )
    (net (code "83") (name "unconnected-(U1B-IO_L1N_A24_VREF_1-PadB20)") (class "Default")
      (node (ref "U1") (pin "B20") (pinfunction "IO_L1N_A24_VREF_1_B20") (pintype "bidirectional"))
    )
    (net (code "84") (name "unconnected-(U1B-IO_L32P_A17_M1A8_1-PadC20)") (class "Default")
      (node (ref "U1") (pin "C20") (pinfunction "IO_L32P_A17_M1A8_1_C20") (pintype "bidirectional"))
    )
    (net (code "85") (name "unconnected-(U1C-IO_L58P_2-PadY3)") (class "Default")
      (node (ref "U1") (pin "Y3") (pinfunction "IO_L58P_2_Y3") (pintype "bidirectional"))
    )
    (net (code "86") (name "unconnected-(U1D-IO_L1N_VREF_3-PadY1)") (class "Default")
      (node (ref "U1") (pin "Y1") (pinfunction "IO_L1N_VREF_3_Y1") (pintype "bidirectional"))
    )
    (net (code "87") (name "unconnected-(U1D-IO_L1P_3-PadY2)") (class "Default")
      (node (ref "U1") (pin "Y2") (pinfunction "IO_L1P_3_Y2") (pintype "bidirectional"))
    )
    (net (code "88") (name "unconnected-(U1D-IO_L2N_3-PadW1)") (class "Default")
      (node (ref "U1") (pin "W1") (pinfunction "IO_L2N_3_W1") (pintype "bidirectional"))
    )
    (net (code "89") (name "unconnected-(U1D-IO_L2P_3-PadW3)") (class "Default")
      (node (ref "U1") (pin "W3") (pinfunction "IO_L2P_3_W3") (pintype "bidirectional"))
    )
    (net (code "90") (name "unconnected-(U1D-IO_L32N_M3DQ15_3-PadV1)") (class "Default")
      (node (ref "U1") (pin "V1") (pinfunction "IO_L32N_M3DQ15_3_V1") (pintype "bidirectional"))
    )
    (net (code "91") (name "unconnected-(U1D-IO_L32P_M3DQ14_3-PadV2)") (class "Default")
      (node (ref "U1") (pin "V2") (pinfunction "IO_L32P_M3DQ14_3_V2") (pintype "bidirectional"))
    )
    (net (code "92") (name "unconnected-(U1D-IO_L34N_M3UDQSN_3-PadT1)") (class "Default")
      (node (ref "U1") (pin "T1") (pinfunction "IO_L34N_M3UDQSN_3_T1") (pintype "bidirectional"))
    )
    (net (code "93") (name "unconnected-(U1D-IO_L34P_M3UDQS_3-PadT2)") (class "Default")
      (node (ref "U1") (pin "T2") (pinfunction "IO_L34P_M3UDQS_3_T2") (pintype "bidirectional"))
    )
    (net (code "94") (name "unconnected-(U1D-IO_L36N_M3DQ9_3-PadP1)") (class "Default")
      (node (ref "U1") (pin "P1") (pinfunction "IO_L36N_M3DQ9_3_P1") (pintype "bidirectional"))
    )
    (net (code "95") (name "unconnected-(U1D-IO_L36P_M3DQ8_3-PadP2)") (class "Default")
      (node (ref "U1") (pin "P2") (pinfunction "IO_L36P_M3DQ8_3_P2") (pintype "bidirectional"))
    )
    (net (code "96") (name "unconnected-(U1D-IO_L38N_M3DQ3_3-PadM1)") (class "Default")
      (node (ref "U1") (pin "M1") (pinfunction "IO_L38N_M3DQ3_3_M1") (pintype "bidirectional"))
    )
    (net (code "97") (name "unconnected-(U1D-IO_L38P_M3DQ2_3-PadM2)") (class "Default")
      (node (ref "U1") (pin "M2") (pinfunction "IO_L38P_M3DQ2_3_M2") (pintype "bidirectional"))
    )
    (net (code "98") (name "unconnected-(U1D-IO_L40N_M3DQ7_3-PadK1)") (class "Default")
      (node (ref "U1") (pin "K1") (pinfunction "IO_L40N_M3DQ7_3_K1") (pintype "bidirectional"))
    )
    (net (code "99") (name "unconnected-(U1D-IO_L40P_M3DQ6_3-PadK2)") (class "Default")
      (node (ref "U1") (pin "K2") (pinfunction "IO_L40P_M3DQ6_3_K2") (pintype "bidirectional"))
    )
    (net (code "100") (name "unconnected-(U1D-IO_L43N_GCLK22_IRDY2_M3CASN_3-PadK4)") (class "Default")
      (node (ref "U1") (pin "K4") (pinfunction "IO_L43N_GCLK22_IRDY2_M3CASN_3_K4") (pintype "bidirectional"))
    )
    (net (code "101") (name "unconnected-(U1D-IO_L43P_GCLK23_M3RASN_3-PadK5)") (class "Default")
      (node (ref "U1") (pin "K5") (pinfunction "IO_L43P_GCLK23_M3RASN_3_K5") (pintype "bidirectional"))
    )
    (net (code "102") (name "unconnected-(U1D-IO_L50N_M3BA2_3-PadF1)") (class "Default")
      (node (ref "U1") (pin "F1") (pinfunction "IO_L50N_M3BA2_3_F1") (pintype "bidirectional"))
    )
    (net (code "103") (name "unconnected-(U1D-IO_L50P_M3WE_3-PadF2)") (class "Default")
      (node (ref "U1") (pin "F2") (pinfunction "IO_L50P_M3WE_3_F2") (pintype "bidirectional"))
    )
    (net (code "104") (name "unconnected-(U1D-IO_L52N_M3A9_3-PadE1)") (class "Default")
      (node (ref "U1") (pin "E1") (pinfunction "IO_L52N_M3A9_3_E1") (pintype "bidirectional"))
    )
    (net (code "105") (name "unconnected-(U1D-IO_L54N_M3A11_3-PadC1)") (class "Default")
      (node (ref "U1") (pin "C1") (pinfunction "IO_L54N_M3A11_3_C1") (pintype "bidirectional"))
    )
    (net (code "106") (name "unconnected-(U1D-IO_L54P_M3RESET_3-PadC3)") (class "Default")
      (node (ref "U1") (pin "C3") (pinfunction "IO_L54P_M3RESET_3_C3") (pintype "bidirectional"))
    )
    (net (code "107") (name "unconnected-(U1D-IO_L83N_VREF_3-PadB3)") (class "Default")
      (node (ref "U1") (pin "B3") (pinfunction "IO_L83N_VREF_3_B3") (pintype "bidirectional"))
    )
    (net (code "108") (name "unconnected-(U1D-IO_L83P_3-PadA2)") (class "Default")
      (node (ref "U1") (pin "A2") (pinfunction "IO_L83P_3_A2") (pintype "bidirectional"))
    )
  )
)
